# 24V0_5A.net
KiCad netlist of a schematic drawn in Altium Designer
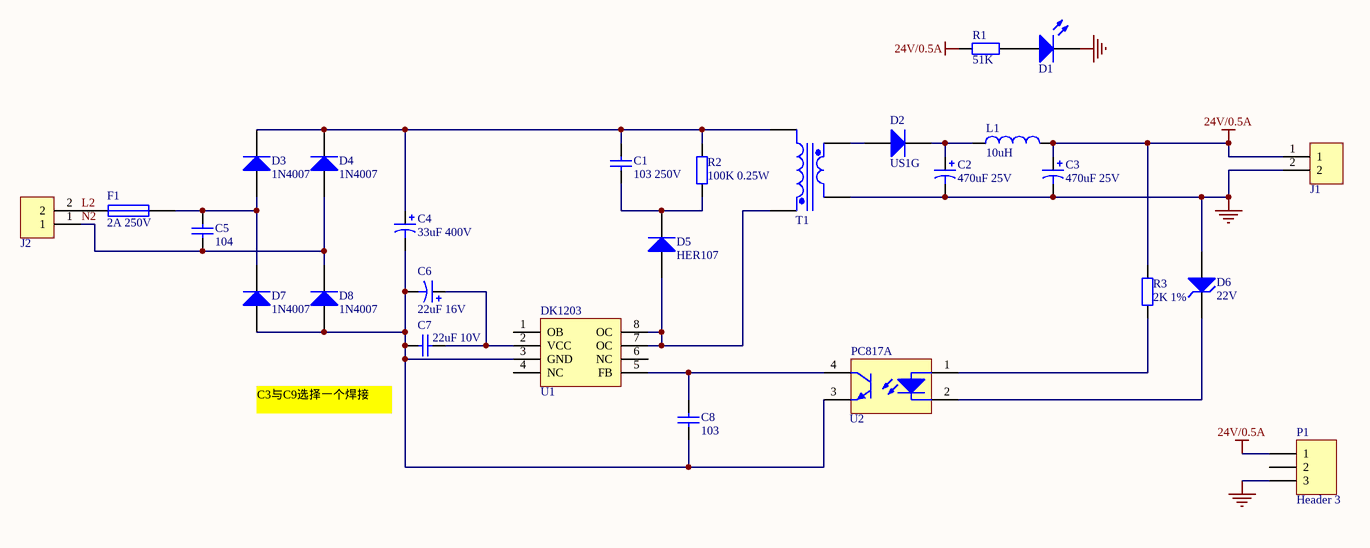
[diagram p0: 24V0.5A.SchDoc]

(export (version "E")
  (design (tool "Eeschema 10.0.6"))
  (components
    (comp (ref "C1") (value "103 250V") (footprint "CAP_0805") (libsource (lib "钦的集成库1") (part "Cap_2")))
    (comp (ref "C2")
      (value "470uF 25V")
      (footprint "CAP POLL 直插电解质8*12/8*16")
      (libsource (lib "钦的集成库1") (part "Cap_"))
    )
    (comp (ref "C3")
      (value "470uF 25V")
      (footprint "CAP POLL 直插电解质8*12/8*16")
      (libsource (lib "钦的集成库1") (part "Cap_"))
    )
    (comp (ref "C4")
      (value "33uF 400V")
      (footprint "Cap POLL 直插电解质 13*20")
      (libsource (lib "钦的集成库1") (part "Cap_"))
    )
    (comp (ref "C5") (value "104") (footprint "Cap安规104") (libsource (lib "钦的集成库1") (part "Cap_2")))
    (comp (ref "C6")
      (value "22uF 16V")
      (footprint "CAP POLL 直插电解质5*12")
      (libsource (lib "钦的集成库1") (part "Cap_"))
    )
    (comp (ref "C7") (value "22uF 10V") (footprint "CAP_0805") (libsource (lib "钦的集成库1") (part "Cap_2")))
    (comp (ref "C8") (value "103") (footprint "CAP瓷片直插") (libsource (lib "钦的集成库1") (part "Cap_2")))
    (comp (ref "D1") (value "LED_") (footprint "LED_0805") (libsource (lib "钦的集成库1") (part "LED_")))
    (comp (ref "D2") (value "US1G") (footprint "DIO_214") (libsource (lib "钦的集成库1") (part "1N4007")))
    (comp (ref "D3") (value "1N4007") (footprint "直插二极管") (libsource (lib "钦的原理图库1") (part "1N4007")))
    (comp (ref "D4") (value "1N4007") (footprint "直插二极管") (libsource (lib "钦的原理图库1") (part "1N4007")))
    (comp (ref "D5") (value "HER107") (footprint "DO-41") (libsource (lib "钦的集成库1") (part "1N4007")))
    (comp (ref "D6") (value "22V") (footprint "LL-34") (libsource (lib "钦的集成库1") (part "稳压二极管")))
    (comp (ref "D7") (value "1N4007") (footprint "直插二极管") (libsource (lib "钦的原理图库1") (part "1N4007")))
    (comp (ref "D8") (value "1N4007") (footprint "直插二极管") (libsource (lib "钦的原理图库1") (part "1N4007")))
    (comp (ref "F1")
      (value "Fuse")
      (footprint "2410")
      (fields (field (name "I HOLD") "2A 250V"))
      (libsource (lib "钦的集成库1") (part "Fuse"))
    )
    (comp (ref "J1") (value "接线端子2P") (footprint "接线端子2P") (libsource (lib "钦的集成库1") (part "接线端子2P")))
    (comp (ref "J2") (value "接线端子2P") (footprint "接线端子2P") (libsource (lib "") (part "接线端子2P_1")))
    (comp (ref "L1")
      (value "10uH")
      (footprint "Inductor_SM4532")
      (fields (field (name "Comment") "Inductor_"))
      (libsource (lib "钦的集成库1") (part "Inductor_"))
    )
    (comp (ref "P1")
      (value "Header 3")
      (footprint "HDR1X3")
      (description "Header, 3-Pin")
      (fields (field (name "PUBLISHER") "Altium Limited"))
      (libsource (lib "Miscellaneous Connectors") (part "Header 3"))
    )
    (comp (ref "R1") (value "51K") (footprint "Res_0805") (libsource (lib "") (part "Res__1")))
    (comp (ref "R2") (value "100K 0.25W") (footprint "1206") (libsource (lib "钦的集成库1") (part "Res_")))
    (comp (ref "R3") (value "2K 1%") (footprint "Res_0805") (libsource (lib "钦的集成库1") (part "Res_")))
    (comp (ref "T1")
      (value "变压器-双边-8引脚")
      (footprint "变压器EE20-5_5-剪脚")
      (libsource (lib "钦的原理图库1") (part "变压器-双边-8引脚"))
    )
    (comp (ref "U1") (value "DK1203") (footprint "DIP-8") (libsource (lib "钦的原理图库1") (part "DK1203")))
    (comp (ref "U2") (value "PC817A") (footprint "DIP-4") (libsource (lib "钦的原理图库1") (part "光耦 - 1")))
  )
  (nets
    (net (code "1") (name "/L2") (class "Default")
      (node (ref "F1") (pin "1") (pinfunction "1_1") (pintype "passive"))
      (node (ref "J2") (pin "2") (pinfunction "2_2") (pintype "power_in"))
    )
    (net (code "2") (name "/N2") (class "Default")
      (node (ref "C5") (pin "1") (pinfunction "1_1") (pintype "passive"))
      (node (ref "D4") (pin "1") (pinfunction "A_1") (pintype "passive"))
      (node (ref "D8") (pin "2") (pinfunction "K_2") (pintype "passive"))
      (node (ref "J2") (pin "1") (pinfunction "1_1") (pintype "power_in"))
    )
    (net (code "3") (name "24V{slash}0.5A") (class "Default")
      (node (ref "C3") (pin "1") (pinfunction "1_1") (pintype "passive"))
      (node (ref "J1") (pin "1") (pinfunction "1_1") (pintype "power_in"))
      (node (ref "L1") (pin "2") (pinfunction "2_2") (pintype "passive"))
      (node (ref "P1") (pin "1") (pinfunction "1_1") (pintype "passive"))
      (node (ref "R1") (pin "2") (pinfunction "2_2") (pintype "passive"))
      (node (ref "R3") (pin "2") (pinfunction "2_2") (pintype "passive"))
    )
    (net (code "4") (name "GND2") (class "Default")
      (node (ref "C2") (pin "2") (pinfunction "2_2") (pintype "passive"))
      (node (ref "C3") (pin "2") (pinfunction "2_2") (pintype "passive"))
      (node (ref "D1") (pin "2") (pinfunction "K_2") (pintype "passive"))
      (node (ref "D6") (pin "1") (pinfunction "A_1") (pintype "passive"))
      (node (ref "J1") (pin "2") (pinfunction "2_2") (pintype "power_in"))
      (node (ref "P1") (pin "3") (pinfunction "3_3") (pintype "passive"))
      (node (ref "T1") (pin "6") (pinfunction "Sec-_6") (pintype "passive"))
    )
    (net (code "5") (name "Net-(D1-A)") (class "Default")
      (node (ref "D1") (pin "1") (pinfunction "A_1") (pintype "passive"))
      (node (ref "R1") (pin "1") (pinfunction "1_1") (pintype "passive"))
    )
    (net (code "6") (name "Net-(D2-A)") (class "Default")
      (node (ref "D2") (pin "1") (pinfunction "A_1") (pintype "passive"))
      (node (ref "T1") (pin "7") (pinfunction "Sec+_7") (pintype "passive"))
    )
    (net (code "7") (name "Net-(D2-K)") (class "Default")
      (node (ref "C2") (pin "1") (pinfunction "1_1") (pintype "passive"))
      (node (ref "D2") (pin "2") (pinfunction "K_2") (pintype "passive"))
      (node (ref "L1") (pin "1") (pinfunction "1_1") (pintype "passive"))
    )
    (net (code "8") (name "Net-(D3-A)") (class "Default")
      (node (ref "C5") (pin "2") (pinfunction "2_2") (pintype "passive"))
      (node (ref "D3") (pin "1") (pinfunction "A_1") (pintype "passive"))
      (node (ref "D7") (pin "2") (pinfunction "K_2") (pintype "passive"))
      (node (ref "F1") (pin "2") (pinfunction "2_2") (pintype "passive"))
    )
    (net (code "9") (name "Net-(D3-K)") (class "Default")
      (node (ref "C1") (pin "2") (pinfunction "2_2") (pintype "passive"))
      (node (ref "C4") (pin "1") (pinfunction "1_1") (pintype "passive"))
      (node (ref "D3") (pin "2") (pinfunction "K_2") (pintype "passive"))
      (node (ref "D4") (pin "2") (pinfunction "K_2") (pintype "passive"))
      (node (ref "R2") (pin "2") (pinfunction "2_2") (pintype "passive"))
      (node (ref "T1") (pin "1") (pinfunction "Pri+_1") (pintype "passive"))
    )
    (net (code "10") (name "Net-(D5-A)") (class "Default")
      (node (ref "D5") (pin "1") (pinfunction "A_1") (pintype "passive"))
      (node (ref "T1") (pin "4") (pinfunction "Pri-_4") (pintype "passive"))
      (node (ref "U1") (pin "7") (pinfunction "OC_7") (pintype "passive"))
      (node (ref "U1") (pin "8") (pinfunction "OC_8") (pintype "passive"))
    )
    (net (code "11") (name "Net-(D5-K)") (class "Default")
      (node (ref "C1") (pin "1") (pinfunction "1_1") (pintype "passive"))
      (node (ref "D5") (pin "2") (pinfunction "K_2") (pintype "passive"))
      (node (ref "R2") (pin "1") (pinfunction "1_1") (pintype "passive"))
    )
    (net (code "12") (name "Net-(D6-K)") (class "Default")
      (node (ref "D6") (pin "2") (pinfunction "K_2") (pintype "passive"))
      (node (ref "U2") (pin "2") (pinfunction "K_2") (pintype "passive"))
    )
    (net (code "13") (name "Net-(D7-A)") (class "Default")
      (node (ref "C4") (pin "2") (pinfunction "2_2") (pintype "passive"))
      (node (ref "C6") (pin "2") (pinfunction "2_2") (pintype "passive"))
      (node (ref "C7") (pin "2") (pinfunction "2_2") (pintype "passive"))
      (node (ref "C8") (pin "1") (pinfunction "1_1") (pintype "passive"))
      (node (ref "D7") (pin "1") (pinfunction "A_1") (pintype "passive"))
      (node (ref "D8") (pin "1") (pinfunction "A_1") (pintype "passive"))
      (node (ref "U1") (pin "3") (pinfunction "GND_3") (pintype "passive"))
      (node (ref "U2") (pin "3") (pinfunction "E_3") (pintype "passive"))
    )
    (net (code "14") (name "Net-(U1-FB)") (class "Default")
      (node (ref "C8") (pin "2") (pinfunction "2_2") (pintype "passive"))
      (node (ref "U1") (pin "5") (pinfunction "FB_5") (pintype "passive"))
      (node (ref "U2") (pin "4") (pinfunction "C_4") (pintype "passive"))
    )
    (net (code "15") (name "Net-(U1-VCC)") (class "Default")
      (node (ref "C6") (pin "1") (pinfunction "1_1") (pintype "passive"))
      (node (ref "C7") (pin "1") (pinfunction "1_1") (pintype "passive"))
      (node (ref "U1") (pin "2") (pinfunction "VCC_2") (pintype "passive"))
    )
    (net (code "16") (name "Net-(U2-A)") (class "Default")
      (node (ref "R3") (pin "1") (pinfunction "1_1") (pintype "passive"))
      (node (ref "U2") (pin "1") (pinfunction "A_1") (pintype "passive"))
    )
    (net (code "17") (name "unconnected-(P1-Pad2)") (class "Default")
      (node (ref "P1") (pin "2") (pinfunction "2_2") (pintype "passive"))
    )
    (net (code "18") (name "unconnected-(U1-NC-Pad4)") (class "Default")
      (node (ref "U1") (pin "4") (pinfunction "NC_4") (pintype "passive"))
    )
    (net (code "19") (name "unconnected-(U1-NC-Pad6)") (class "Default")
      (node (ref "U1") (pin "6") (pinfunction "NC_6") (pintype "passive"))
    )
    (net (code "20") (name "unconnected-(U1-OB-Pad1)") (class "Default")
      (node (ref "U1") (pin "1") (pinfunction "OB_1") (pintype "passive"))
    )
  )
)
